# programmer8_0.net
KiCad netlist of a schematic drawn in EAGLE
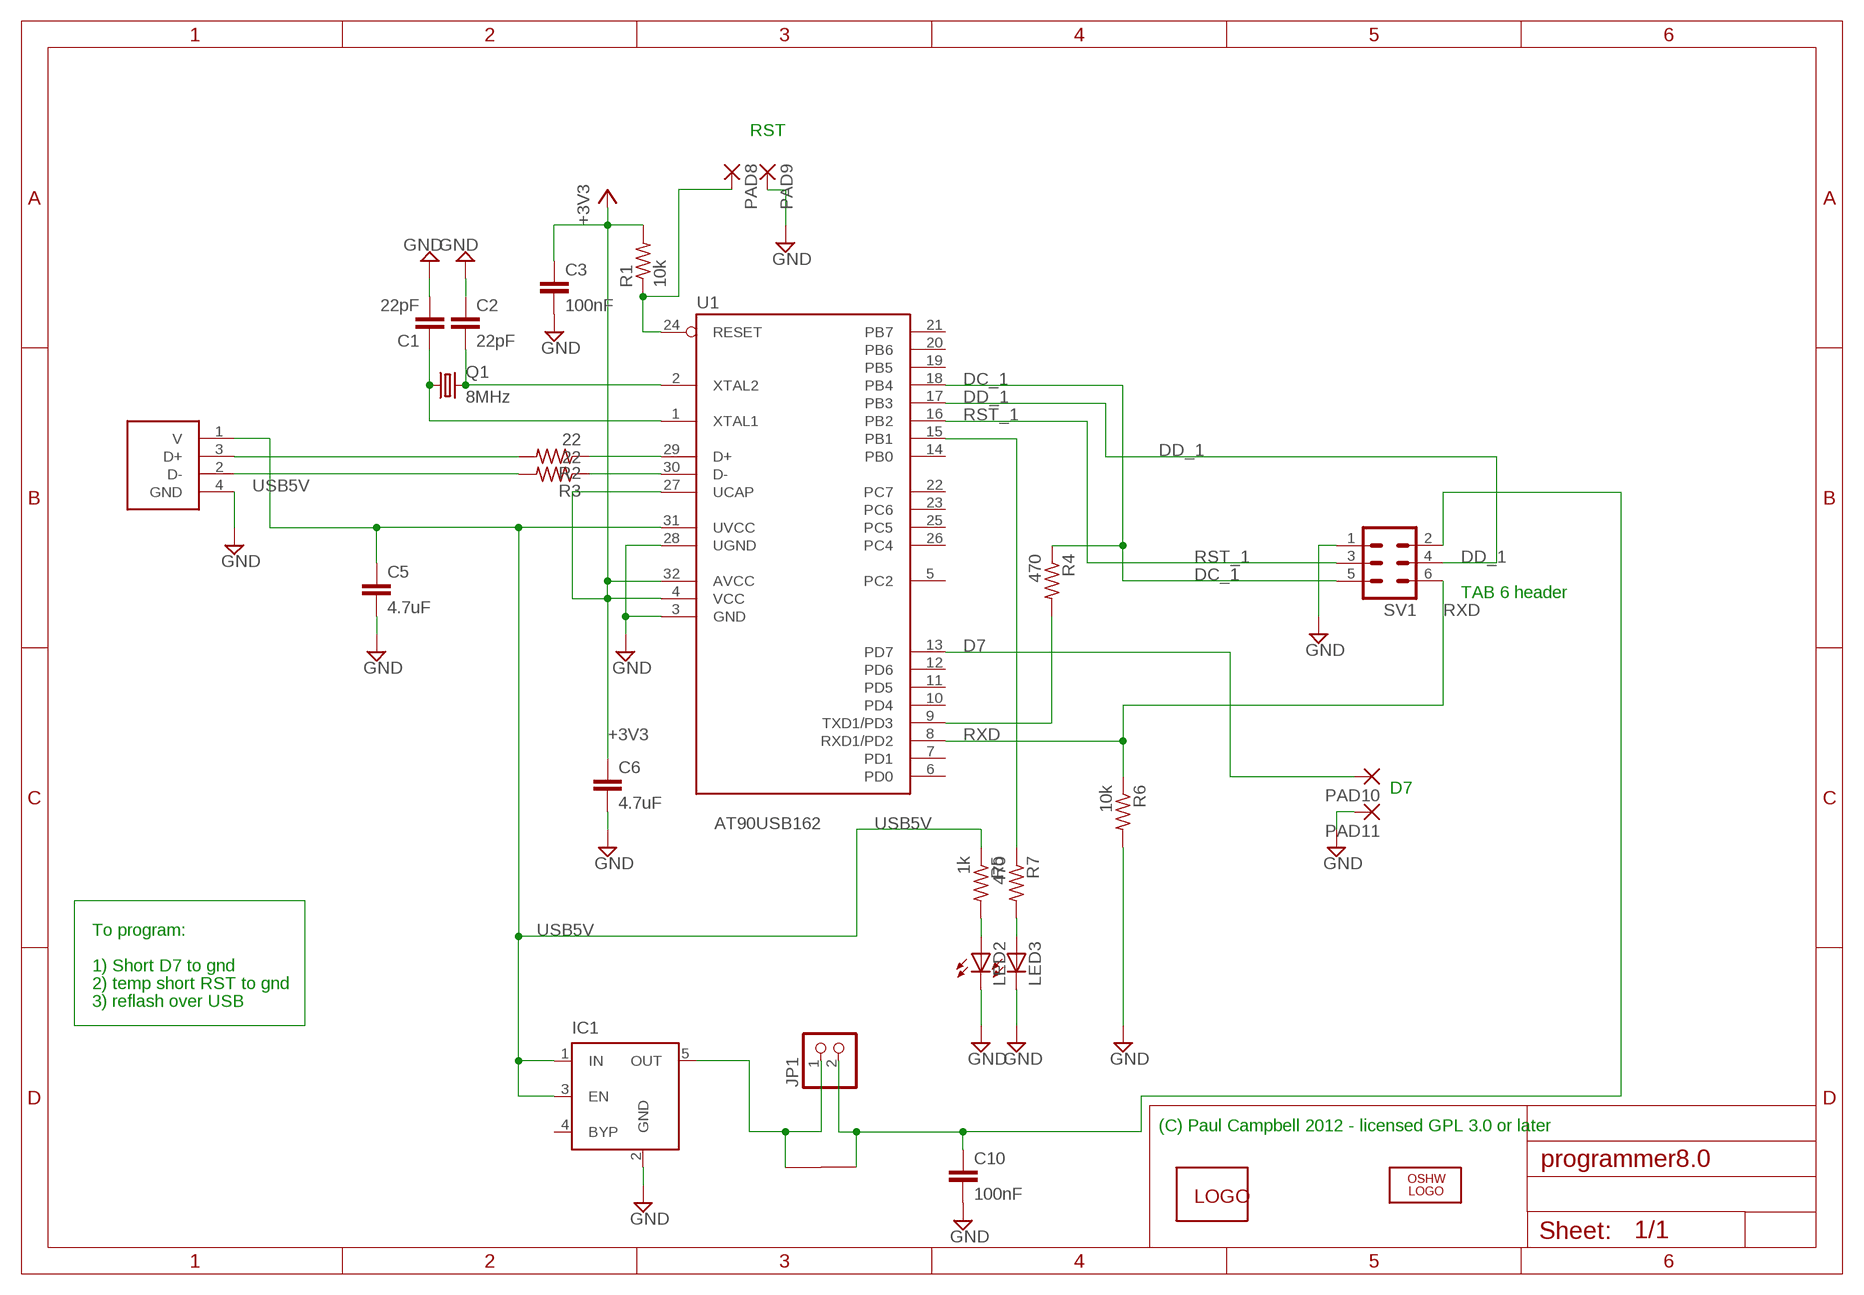
[diagram p0: schematic, sheet 1]

(export (version "E")
  (design (tool "Eeschema 10.0.6"))
  (components
    (comp (ref "C1")
      (value "22pF")
      (footprint "eagle-import:C0603")
      (libsource (lib "eagle-import") (part "C-EUC0603"))
    )
    (comp (ref "C2")
      (value "22pF")
      (footprint "eagle-import:C0603")
      (libsource (lib "eagle-import") (part "C-EUC0603"))
    )
    (comp (ref "C3")
      (value "100nF")
      (footprint "eagle-import:C0603")
      (libsource (lib "eagle-import") (part "C-EUC0603"))
    )
    (comp (ref "C5")
      (value "4.7uF")
      (footprint "eagle-import:C0805")
      (libsource (lib "eagle-import") (part "C-EUC0805"))
    )
    (comp (ref "C6")
      (value "4.7uF")
      (footprint "eagle-import:C0805")
      (libsource (lib "eagle-import") (part "C-EUC0805"))
    )
    (comp (ref "C10")
      (value "100nF")
      (footprint "eagle-import:C0603")
      (libsource (lib "eagle-import") (part "C-EUC0603"))
    )
    (comp (ref "IC1")
      (value "MIC5219XX")
      (footprint "eagle-import:SOT23-5")
      (libsource (lib "eagle-import") (part "MIC5219XX"))
    )
    (comp (ref "JP1")
      (value "PINHD-1X2")
      (footprint "eagle-import:1X02")
      (libsource (lib "eagle-import") (part "PINHD-1X2"))
    )
    (comp (ref "LED2")
      (value "LEDCHIP-LED0805")
      (footprint "eagle-import:CHIP-LED0805")
      (libsource (lib "eagle-import") (part "LEDCHIP-LED0805"))
    )
    (comp (ref "LED3")
      (value "LEDCHIP-LED0805")
      (footprint "eagle-import:CHIP-LED0805")
      (libsource (lib "eagle-import") (part "LEDCHIP-LED0805"))
    )
    (comp (ref "LOGO2")
      (value "OSHW_LOGO_FILLX0100-NT")
      (footprint "eagle-import:OSHW_FILLX100_NOTEXT")
      (libsource (lib "eagle-import") (part "OSHW_LOGO_FILLX0100-NT"))
    )
    (comp (ref "PAD8")
      (value "1,6/0,8")
      (footprint "eagle-import:1,6_0,8")
      (libsource (lib "eagle-import") (part "1,6/0,8"))
    )
    (comp (ref "PAD9")
      (value "1,6/0,8")
      (footprint "eagle-import:1,6_0,8")
      (libsource (lib "eagle-import") (part "1,6/0,8"))
    )
    (comp (ref "PAD10")
      (value "1,6/0,8")
      (footprint "eagle-import:1,6_0,8")
      (libsource (lib "eagle-import") (part "1,6/0,8"))
    )
    (comp (ref "PAD11")
      (value "1,6/0,8")
      (footprint "eagle-import:1,6_0,8")
      (libsource (lib "eagle-import") (part "1,6/0,8"))
    )
    (comp (ref "Q1")
      (value "8MHz")
      (footprint "eagle-import:HC49UP")
      (libsource (lib "eagle-import") (part "CRYSTALHC49UP"))
    )
    (comp (ref "R1")
      (value "10k")
      (footprint "eagle-import:R0603")
      (libsource (lib "eagle-import") (part "R-US_R0603"))
    )
    (comp (ref "R2")
      (value "22")
      (footprint "eagle-import:R0603")
      (libsource (lib "eagle-import") (part "R-US_R0603"))
    )
    (comp (ref "R3")
      (value "22")
      (footprint "eagle-import:R0603")
      (libsource (lib "eagle-import") (part "R-US_R0603"))
    )
    (comp (ref "R4")
      (value "470")
      (footprint "eagle-import:R0603")
      (libsource (lib "eagle-import") (part "R-US_R0603"))
    )
    (comp (ref "R5")
      (value "1k")
      (footprint "eagle-import:R0603")
      (libsource (lib "eagle-import") (part "R-US_R0603"))
    )
    (comp (ref "R6")
      (value "10k")
      (footprint "eagle-import:R0603")
      (libsource (lib "eagle-import") (part "R-US_R0603"))
    )
    (comp (ref "R7")
      (value "470")
      (footprint "eagle-import:R0603")
      (libsource (lib "eagle-import") (part "R-US_R0603"))
    )
    (comp (ref "SV1")
      (value "MA03-2")
      (footprint "eagle-import:MA03-2")
      (libsource (lib "eagle-import") (part "MA03-2"))
    )
    (comp (ref "U$1")
      (value "LINK")
      (footprint "eagle-import:LINK")
      (libsource (lib "eagle-import") (part "LINK"))
    )
    (comp (ref "U$2")
      (value "MOONBASE-LOGO")
      (footprint "eagle-import:MOONBASE-LOGO")
      (libsource (lib "eagle-import") (part "MOONBASE-LOGO"))
    )
    (comp (ref "U$3")
      (value "USB-RAW")
      (footprint "eagle-import:RAW-USB")
      (libsource (lib "eagle-import") (part "USB-RAW"))
    )
    (comp (ref "U1")
      (value "AT90USB162")
      (footprint "eagle-import:TQFP32-08")
      (libsource (lib "eagle-import") (part "AT90USB162"))
    )
  )
  (nets
    (net (code "1") (name "+3V3") (class "Default")
      (node (ref "C3") (pin "1") (pinfunction "1_1") (pintype "passive"))
      (node (ref "C6") (pin "1") (pinfunction "1_1") (pintype "passive"))
      (node (ref "R1") (pin "2") (pinfunction "2_2") (pintype "passive"))
      (node (ref "U1") (pin "27") (pinfunction "UCAP_27") (pintype "bidirectional"))
      (node (ref "U1") (pin "32") (pinfunction "AVCC_32") (pintype "bidirectional"))
      (node (ref "U1") (pin "4") (pinfunction "VCC_4") (pintype "bidirectional"))
    )
    (net (code "2") (name "/D7") (class "Default")
      (node (ref "PAD10") (pin "1") (pinfunction "P_1") (pintype "passive"))
      (node (ref "U1") (pin "13") (pinfunction "PD7_13") (pintype "bidirectional"))
    )
    (net (code "3") (name "/DC_1") (class "Default")
      (node (ref "R4") (pin "1") (pinfunction "1_1") (pintype "passive"))
      (node (ref "SV1") (pin "5") (pinfunction "5_5") (pintype "passive"))
      (node (ref "U1") (pin "18") (pinfunction "PB4_18") (pintype "bidirectional"))
    )
    (net (code "4") (name "/DD_1") (class "Default")
      (node (ref "SV1") (pin "4") (pinfunction "4_4") (pintype "passive"))
      (node (ref "U1") (pin "17") (pinfunction "PB3_17") (pintype "bidirectional"))
    )
    (net (code "5") (name "/RST_1") (class "Default")
      (node (ref "SV1") (pin "3") (pinfunction "3_3") (pintype "passive"))
      (node (ref "U1") (pin "16") (pinfunction "PB2_16") (pintype "bidirectional"))
    )
    (net (code "6") (name "/RXD") (class "Default")
      (node (ref "R6") (pin "1") (pinfunction "1_1") (pintype "passive"))
      (node (ref "SV1") (pin "6") (pinfunction "6_6") (pintype "passive"))
      (node (ref "U1") (pin "8") (pinfunction "RXD1/PD2_8") (pintype "bidirectional"))
    )
    (net (code "7") (name "/USB5V") (class "Default")
      (node (ref "C5") (pin "1") (pinfunction "1_1") (pintype "passive"))
      (node (ref "IC1") (pin "1") (pinfunction "IN_1") (pintype "input"))
      (node (ref "IC1") (pin "3") (pinfunction "EN_3") (pintype "input"))
      (node (ref "R5") (pin "1") (pinfunction "1_1") (pintype "passive"))
      (node (ref "U$3") (pin "1") (pinfunction "V_1") (pintype "bidirectional"))
      (node (ref "U1") (pin "31") (pinfunction "UVCC_31") (pintype "power_in"))
    )
    (net (code "8") (name "GND") (class "Default")
      (node (ref "C1") (pin "2") (pinfunction "2_2") (pintype "passive"))
      (node (ref "C10") (pin "2") (pinfunction "2_2") (pintype "passive"))
      (node (ref "C2") (pin "1") (pinfunction "1_1") (pintype "passive"))
      (node (ref "C3") (pin "2") (pinfunction "2_2") (pintype "passive"))
      (node (ref "C5") (pin "2") (pinfunction "2_2") (pintype "passive"))
      (node (ref "C6") (pin "2") (pinfunction "2_2") (pintype "passive"))
      (node (ref "IC1") (pin "2") (pinfunction "GND_2") (pintype "power_in"))
      (node (ref "LED2") (pin "C") (pinfunction "C_C") (pintype "passive"))
      (node (ref "LED3") (pin "C") (pinfunction "C_C") (pintype "passive"))
      (node (ref "PAD11") (pin "1") (pinfunction "P_1") (pintype "passive"))
      (node (ref "PAD9") (pin "1") (pinfunction "P_1") (pintype "passive"))
      (node (ref "R6") (pin "2") (pinfunction "2_2") (pintype "passive"))
      (node (ref "SV1") (pin "1") (pinfunction "1_1") (pintype "passive"))
      (node (ref "U$3") (pin "4") (pinfunction "GND_4") (pintype "bidirectional"))
      (node (ref "U1") (pin "28") (pinfunction "UGND_28") (pintype "power_in"))
      (node (ref "U1") (pin "3") (pinfunction "GND_3") (pintype "bidirectional"))
    )
    (net (code "9") (name "Net-(IC1-OUT)") (class "Default")
      (node (ref "IC1") (pin "5") (pinfunction "OUT_5") (pintype "output"))
      (node (ref "JP1") (pin "1") (pinfunction "1_1") (pintype "passive"))
      (node (ref "U$1") (pin "1") (pinfunction "P$1_1") (pintype "bidirectional"))
    )
    (net (code "10") (name "Net-(LED2-PadA)") (class "Default")
      (node (ref "LED2") (pin "A") (pinfunction "A_A") (pintype "passive"))
      (node (ref "R5") (pin "2") (pinfunction "2_2") (pintype "passive"))
    )
    (net (code "11") (name "Net-(LED3-PadA)") (class "Default")
      (node (ref "LED3") (pin "A") (pinfunction "A_A") (pintype "passive"))
      (node (ref "R7") (pin "2") (pinfunction "2_2") (pintype "passive"))
    )
    (net (code "12") (name "Net-(PAD8-P)") (class "Default")
      (node (ref "PAD8") (pin "1") (pinfunction "P_1") (pintype "passive"))
      (node (ref "R1") (pin "1") (pinfunction "1_1") (pintype "passive"))
      (node (ref "U1") (pin "24") (pinfunction "RESET_24") (pintype "input"))
    )
    (net (code "13") (name "Net-(U$1-P$2)") (class "Default")
      (node (ref "C10") (pin "1") (pinfunction "1_1") (pintype "passive"))
      (node (ref "JP1") (pin "2") (pinfunction "2_2") (pintype "passive"))
      (node (ref "SV1") (pin "2") (pinfunction "2_2") (pintype "passive"))
      (node (ref "U$1") (pin "2") (pinfunction "P$2_2") (pintype "bidirectional"))
    )
    (net (code "14") (name "Net-(U$3-D+)") (class "Default")
      (node (ref "R2") (pin "2") (pinfunction "2_2") (pintype "passive"))
      (node (ref "U$3") (pin "3") (pinfunction "D+_3") (pintype "bidirectional"))
    )
    (net (code "15") (name "Net-(U$3-D-)") (class "Default")
      (node (ref "R3") (pin "2") (pinfunction "2_2") (pintype "passive"))
      (node (ref "U$3") (pin "2") (pinfunction "D-_2") (pintype "bidirectional"))
    )
    (net (code "16") (name "Net-(U1-D+)") (class "Default")
      (node (ref "R2") (pin "1") (pinfunction "1_1") (pintype "passive"))
      (node (ref "U1") (pin "29") (pinfunction "D+_29") (pintype "bidirectional"))
    )
    (net (code "17") (name "Net-(U1-D-)") (class "Default")
      (node (ref "R3") (pin "1") (pinfunction "1_1") (pintype "passive"))
      (node (ref "U1") (pin "30") (pinfunction "D-_30") (pintype "bidirectional"))
    )
    (net (code "18") (name "Net-(U1-PB1)") (class "Default")
      (node (ref "R7") (pin "1") (pinfunction "1_1") (pintype "passive"))
      (node (ref "U1") (pin "15") (pinfunction "PB1_15") (pintype "bidirectional"))
    )
    (net (code "19") (name "Net-(U1-TXD1{slash}PD3)") (class "Default")
      (node (ref "R4") (pin "2") (pinfunction "2_2") (pintype "passive"))
      (node (ref "U1") (pin "9") (pinfunction "TXD1/PD3_9") (pintype "bidirectional"))
    )
    (net (code "20") (name "Net-(U1-XTAL1)") (class "Default")
      (node (ref "C1") (pin "1") (pinfunction "1_1") (pintype "passive"))
      (node (ref "Q1") (pin "1") (pinfunction "1_1") (pintype "passive"))
      (node (ref "U1") (pin "1") (pinfunction "XTAL1_1") (pintype "bidirectional"))
    )
    (net (code "21") (name "Net-(U1-XTAL2)") (class "Default")
      (node (ref "C2") (pin "2") (pinfunction "2_2") (pintype "passive"))
      (node (ref "Q1") (pin "2") (pinfunction "2_2") (pintype "passive"))
      (node (ref "U1") (pin "2") (pinfunction "XTAL2_2") (pintype "bidirectional"))
    )
    (net (code "22") (name "unconnected-(IC1-BYP-Pad4)") (class "Default")
      (node (ref "IC1") (pin "4") (pinfunction "BYP_4") (pintype "passive"))
    )
    (net (code "23") (name "unconnected-(U1-PB0-Pad14)") (class "Default")
      (node (ref "U1") (pin "14") (pinfunction "PB0_14") (pintype "bidirectional"))
    )
    (net (code "24") (name "unconnected-(U1-PB5-Pad19)") (class "Default")
      (node (ref "U1") (pin "19") (pinfunction "PB5_19") (pintype "bidirectional"))
    )
    (net (code "25") (name "unconnected-(U1-PB6-Pad20)") (class "Default")
      (node (ref "U1") (pin "20") (pinfunction "PB6_20") (pintype "bidirectional"))
    )
    (net (code "26") (name "unconnected-(U1-PB7-Pad21)") (class "Default")
      (node (ref "U1") (pin "21") (pinfunction "PB7_21") (pintype "bidirectional"))
    )
    (net (code "27") (name "unconnected-(U1-PC2-Pad5)") (class "Default")
      (node (ref "U1") (pin "5") (pinfunction "PC2_5") (pintype "bidirectional"))
    )
    (net (code "28") (name "unconnected-(U1-PC4-Pad26)") (class "Default")
      (node (ref "U1") (pin "26") (pinfunction "PC4_26") (pintype "bidirectional"))
    )
    (net (code "29") (name "unconnected-(U1-PC5-Pad25)") (class "Default")
      (node (ref "U1") (pin "25") (pinfunction "PC5_25") (pintype "bidirectional"))
    )
    (net (code "30") (name "unconnected-(U1-PC6-Pad23)") (class "Default")
      (node (ref "U1") (pin "23") (pinfunction "PC6_23") (pintype "bidirectional"))
    )
    (net (code "31") (name "unconnected-(U1-PC7-Pad22)") (class "Default")
      (node (ref "U1") (pin "22") (pinfunction "PC7_22") (pintype "bidirectional"))
    )
    (net (code "32") (name "unconnected-(U1-PD0-Pad6)") (class "Default")
      (node (ref "U1") (pin "6") (pinfunction "PD0_6") (pintype "bidirectional"))
    )
    (net (code "33") (name "unconnected-(U1-PD1-Pad7)") (class "Default")
      (node (ref "U1") (pin "7") (pinfunction "PD1_7") (pintype "bidirectional"))
    )
    (net (code "34") (name "unconnected-(U1-PD4-Pad10)") (class "Default")
      (node (ref "U1") (pin "10") (pinfunction "PD4_10") (pintype "bidirectional"))
    )
    (net (code "35") (name "unconnected-(U1-PD5-Pad11)") (class "Default")
      (node (ref "U1") (pin "11") (pinfunction "PD5_11") (pintype "bidirectional"))
    )
    (net (code "36") (name "unconnected-(U1-PD6-Pad12)") (class "Default")
      (node (ref "U1") (pin "12") (pinfunction "PD6_12") (pintype "bidirectional"))
    )
  )
)
